# pico-fmeter-AS65-2.net
KiCad netlist of a schematic drawn in Altium Designer
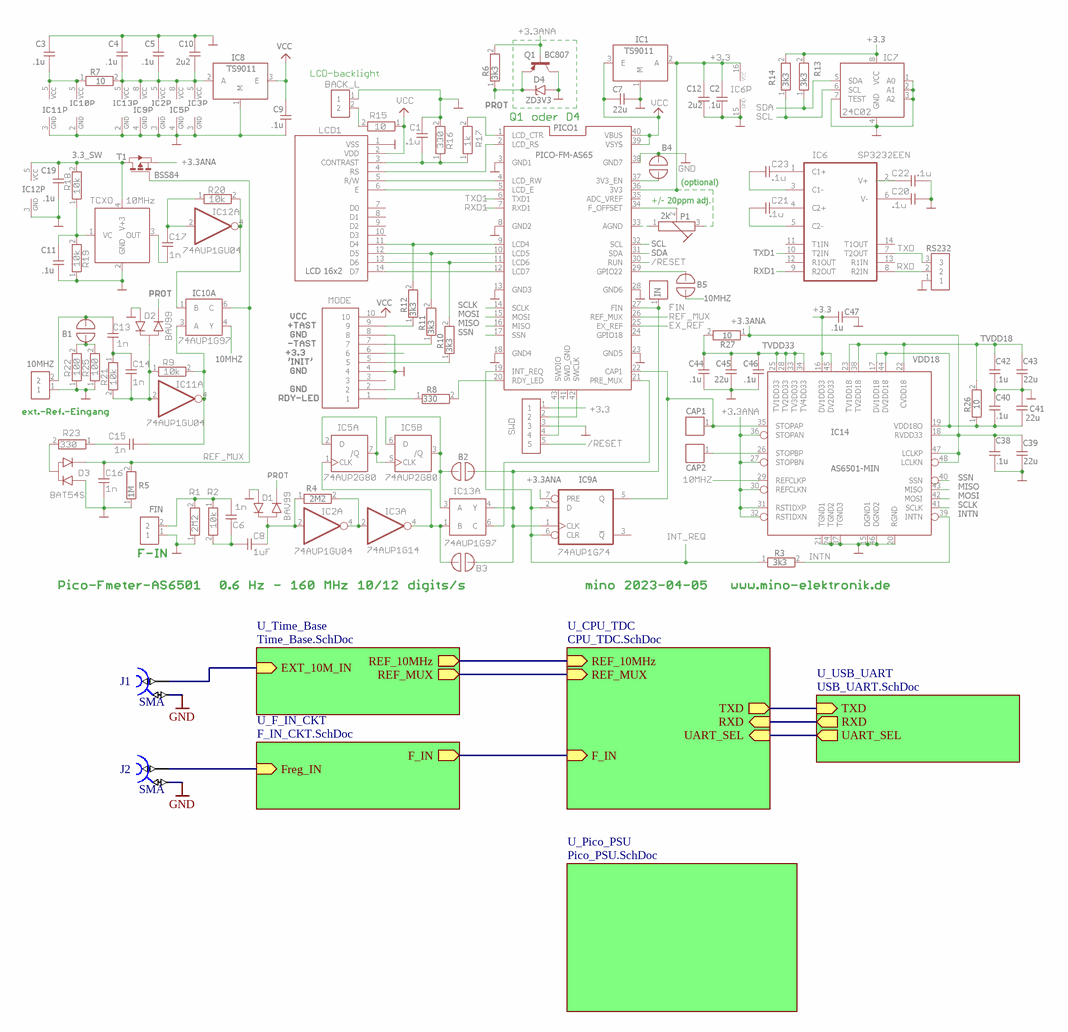
[diagram p0: pico-fmeter-AS65-2.SchDoc]

(export (version "E")
  (design (tool "Eeschema 10.0.6"))
  (components
    (comp (ref "J1")
      (value "SMA")
      (footprint "JOHNSON_142-0701-871")
      (fields
        (field (name "PART NUMBER") "JOHNSON_142-0701-871")
        (field (name "MANUFACTURER") "JOHNSON")
        (field (name "MANUFACTURER PART NUMBER") "142-0701-871")
        (field (name "AUTHOR") "CERN DEM JLC")
      )
      (libsource (lib "Connectors") (part "Coax_1Female_1Shield"))
    )
    (comp (ref "J2")
      (value "SMA")
      (footprint "JOHNSON_142-0701-871")
      (fields
        (field (name "PART NUMBER") "JOHNSON_142-0701-871")
        (field (name "MANUFACTURER") "JOHNSON")
        (field (name "MANUFACTURER PART NUMBER") "142-0701-871")
        (field (name "AUTHOR") "CERN DEM JLC")
      )
      (libsource (lib "Connectors") (part "Coax_1Female_1Shield"))
    )
  )
  (nets
    (net (code "1") (name "/EXT_10M_IN") (class "Default")
      (node (ref "J1") (pin "1") (pinfunction "1_1") (pintype "bidirectional"))
    )
    (net (code "3") (name "/Freg_IN") (class "Default")
      (node (ref "J2") (pin "1") (pinfunction "1_1") (pintype "bidirectional"))
    )
    (net (code "9") (name "GND") (class "Default")
      (node (ref "J1") (pin "2") (pinfunction "2_2") (pintype "bidirectional"))
      (node (ref "J2") (pin "2") (pinfunction "2_2") (pintype "bidirectional"))
    )
  )
)
